# 13_LMS3_Power.net
KiCad netlist of a schematic drawn in Altium Designer
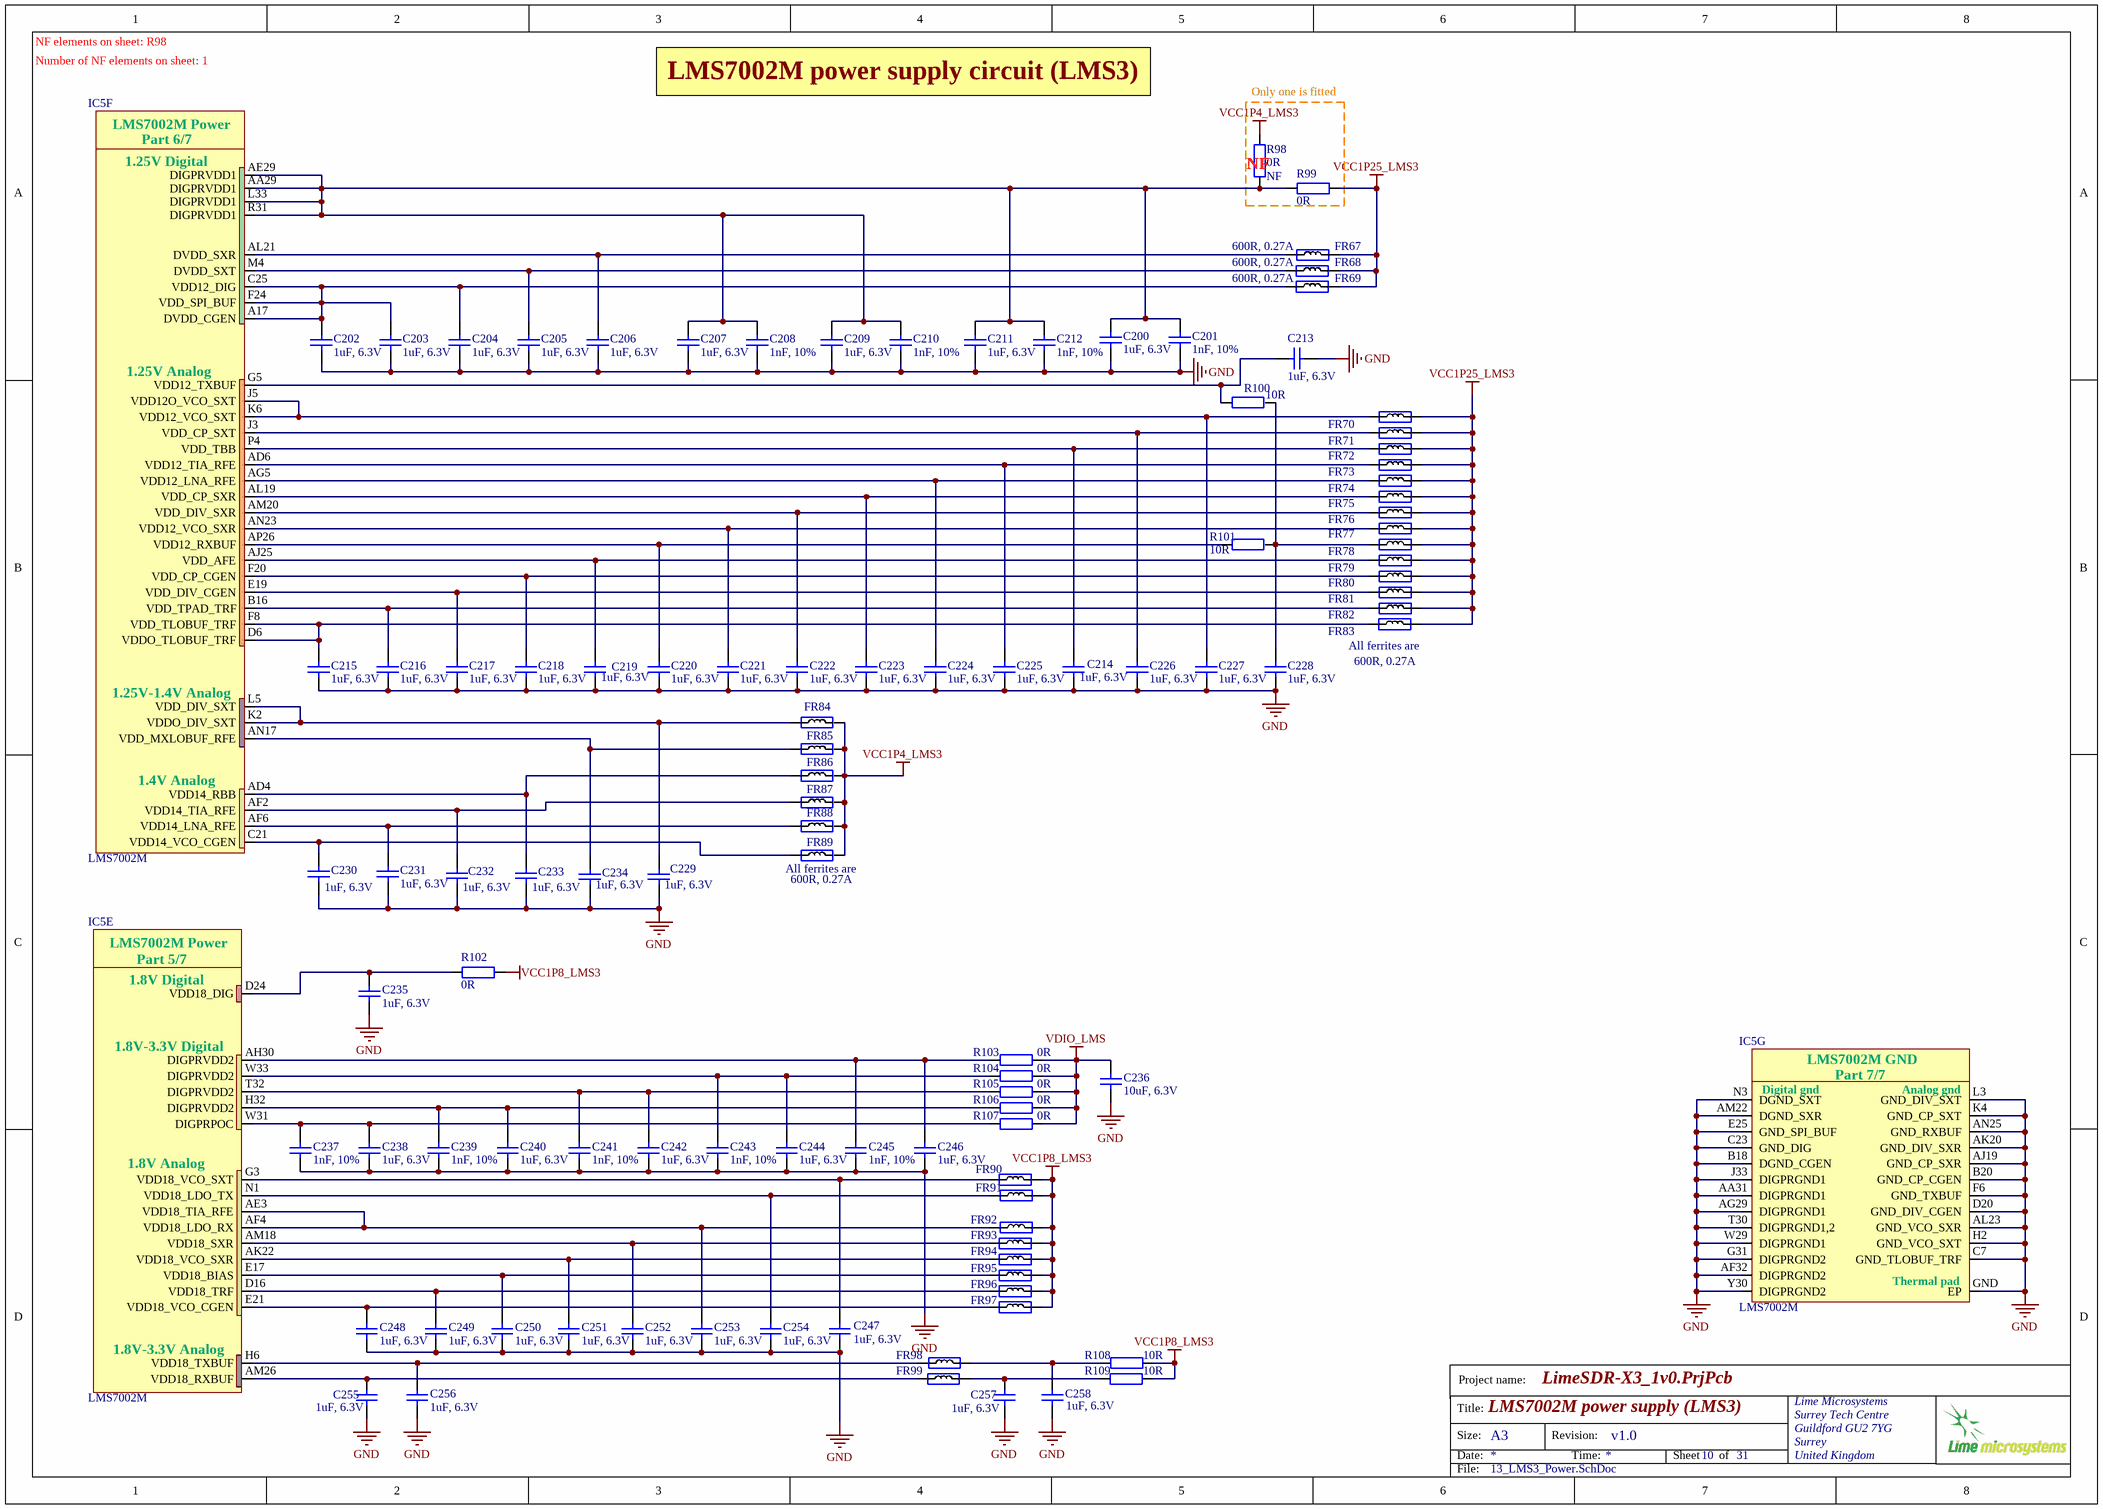
[diagram p0: 13_LMS3_Power.SchDoc]

(export (version "E")
  (design (tool "Eeschema 10.0.6"))
  (components
    (comp (ref "C200")
      (value "1uF, 6.3V")
      (footprint "CAP0201")
      (fields (field (name "TOLERANCE") "±20%") (field (name "MANUFACTURER") "TDK Corporation"))
      (libsource (lib "") (part "Cap_0402_1"))
    )
    (comp (ref "C201")
      (value "1nF, 10%")
      (footprint "CAP0201")
      (fields (field (name "TOLERANCE") "±10%") (field (name "MANUFACTURER") "TDK Corporation"))
      (libsource (lib "") (part "Cap_0402_1"))
    )
    (comp (ref "C202")
      (value "1uF, 6.3V")
      (footprint "CAP0201")
      (fields (field (name "TOLERANCE") "±20%") (field (name "MANUFACTURER") "TDK Corporation"))
      (libsource (lib "") (part "Cap_0402_2"))
    )
    (comp (ref "C203")
      (value "1uF, 6.3V")
      (footprint "CAP0201")
      (fields (field (name "TOLERANCE") "±20%") (field (name "MANUFACTURER") "TDK Corporation"))
      (libsource (lib "") (part "Cap_0402_2"))
    )
    (comp (ref "C204")
      (value "1uF, 6.3V")
      (footprint "CAP0201")
      (fields (field (name "TOLERANCE") "±20%") (field (name "MANUFACTURER") "TDK Corporation"))
      (libsource (lib "") (part "Cap_0402_2"))
    )
    (comp (ref "C205")
      (value "1uF, 6.3V")
      (footprint "CAP0201")
      (fields (field (name "TOLERANCE") "±20%") (field (name "MANUFACTURER") "TDK Corporation"))
      (libsource (lib "") (part "Cap_0402_1"))
    )
    (comp (ref "C206")
      (value "1uF, 6.3V")
      (footprint "CAP0201")
      (fields (field (name "TOLERANCE") "±20%") (field (name "MANUFACTURER") "TDK Corporation"))
      (libsource (lib "") (part "Cap_0402_2"))
    )
    (comp (ref "C207")
      (value "1uF, 6.3V")
      (footprint "CAP0201")
      (fields (field (name "TOLERANCE") "±20%") (field (name "MANUFACTURER") "TDK Corporation"))
      (libsource (lib "") (part "Cap_0402_1"))
    )
    (comp (ref "C208")
      (value "1nF, 10%")
      (footprint "CAP0201")
      (fields (field (name "TOLERANCE") "±10%") (field (name "MANUFACTURER") "TDK Corporation"))
      (libsource (lib "") (part "Cap_0402_1"))
    )
    (comp (ref "C209")
      (value "1uF, 6.3V")
      (footprint "CAP0201")
      (fields (field (name "TOLERANCE") "±20%") (field (name "MANUFACTURER") "TDK Corporation"))
      (libsource (lib "") (part "Cap_0402_1"))
    )
    (comp (ref "C210")
      (value "1nF, 10%")
      (footprint "CAP0201")
      (fields (field (name "TOLERANCE") "±10%") (field (name "MANUFACTURER") "TDK Corporation"))
      (libsource (lib "") (part "Cap_0402_1"))
    )
    (comp (ref "C211")
      (value "1uF, 6.3V")
      (footprint "CAP0201")
      (fields (field (name "TOLERANCE") "±20%") (field (name "MANUFACTURER") "TDK Corporation"))
      (libsource (lib "") (part "Cap_0402_1"))
    )
    (comp (ref "C212")
      (value "1nF, 10%")
      (footprint "CAP0201")
      (fields (field (name "TOLERANCE") "±10%") (field (name "MANUFACTURER") "TDK Corporation"))
      (libsource (lib "") (part "Cap_0402_1"))
    )
    (comp (ref "C213")
      (value "1uF, 6.3V")
      (footprint "CAP0201")
      (fields (field (name "TOLERANCE") "±20%") (field (name "MANUFACTURER") "TDK Corporation"))
      (libsource (lib "") (part "Cap_0402_4"))
    )
    (comp (ref "C214")
      (value "1uF, 6.3V")
      (footprint "CAP0201")
      (fields (field (name "TOLERANCE") "±20%") (field (name "MANUFACTURER") "TDK Corporation"))
      (libsource (lib "") (part "Cap_0402_2"))
    )
    (comp (ref "C215")
      (value "1uF, 6.3V")
      (footprint "CAP0201")
      (fields (field (name "TOLERANCE") "±20%") (field (name "MANUFACTURER") "TDK Corporation"))
      (libsource (lib "") (part "Cap_0402_2"))
    )
    (comp (ref "C216")
      (value "1uF, 6.3V")
      (footprint "CAP0201")
      (fields (field (name "TOLERANCE") "±20%") (field (name "MANUFACTURER") "TDK Corporation"))
      (libsource (lib "") (part "Cap_0402_2"))
    )
    (comp (ref "C217")
      (value "1uF, 6.3V")
      (footprint "CAP0201")
      (fields (field (name "TOLERANCE") "±20%") (field (name "MANUFACTURER") "TDK Corporation"))
      (libsource (lib "") (part "Cap_0402_2"))
    )
    (comp (ref "C218")
      (value "1uF, 6.3V")
      (footprint "CAP0201")
      (fields (field (name "TOLERANCE") "±20%") (field (name "MANUFACTURER") "TDK Corporation"))
      (libsource (lib "") (part "Cap_0402_1"))
    )
    (comp (ref "C219")
      (value "1uF, 6.3V")
      (footprint "CAP0201")
      (fields (field (name "TOLERANCE") "±20%") (field (name "MANUFACTURER") "TDK Corporation"))
      (libsource (lib "") (part "Cap_0402_2"))
    )
    (comp (ref "C220")
      (value "1uF, 6.3V")
      (footprint "CAP0201")
      (fields (field (name "TOLERANCE") "±20%") (field (name "MANUFACTURER") "TDK Corporation"))
      (libsource (lib "") (part "Cap_0402_2"))
    )
    (comp (ref "C221")
      (value "1uF, 6.3V")
      (footprint "CAP0201")
      (fields (field (name "TOLERANCE") "±20%") (field (name "MANUFACTURER") "TDK Corporation"))
      (libsource (lib "") (part "Cap_0402_2"))
    )
    (comp (ref "C222")
      (value "1uF, 6.3V")
      (footprint "CAP0201")
      (fields (field (name "TOLERANCE") "±20%") (field (name "MANUFACTURER") "TDK Corporation"))
      (libsource (lib "") (part "Cap_0402_2"))
    )
    (comp (ref "C223")
      (value "1uF, 6.3V")
      (footprint "CAP0201")
      (fields (field (name "TOLERANCE") "±20%") (field (name "MANUFACTURER") "TDK Corporation"))
      (libsource (lib "") (part "Cap_0402_2"))
    )
    (comp (ref "C224")
      (value "1uF, 6.3V")
      (footprint "CAP0201")
      (fields (field (name "TOLERANCE") "±20%") (field (name "MANUFACTURER") "TDK Corporation"))
      (libsource (lib "") (part "Cap_0402_2"))
    )
    (comp (ref "C225")
      (value "1uF, 6.3V")
      (footprint "CAP0201")
      (fields (field (name "TOLERANCE") "±20%") (field (name "MANUFACTURER") "TDK Corporation"))
      (libsource (lib "") (part "Cap_0402_1"))
    )
    (comp (ref "C226")
      (value "1uF, 6.3V")
      (footprint "CAP0201")
      (fields (field (name "TOLERANCE") "±20%") (field (name "MANUFACTURER") "TDK Corporation"))
      (libsource (lib "") (part "Cap_0402_2"))
    )
    (comp (ref "C227")
      (value "1uF, 6.3V")
      (footprint "CAP0201")
      (fields (field (name "TOLERANCE") "±20%") (field (name "MANUFACTURER") "TDK Corporation"))
      (libsource (lib "") (part "Cap_0402_1"))
    )
    (comp (ref "C228")
      (value "1uF, 6.3V")
      (footprint "CAP0201")
      (fields (field (name "TOLERANCE") "±20%") (field (name "MANUFACTURER") "TDK Corporation"))
      (libsource (lib "") (part "Cap_0402_1"))
    )
    (comp (ref "C229")
      (value "1uF, 6.3V")
      (footprint "CAP0201")
      (fields (field (name "TOLERANCE") "±20%") (field (name "MANUFACTURER") "TDK Corporation"))
      (libsource (lib "") (part "Cap_0402_2"))
    )
    (comp (ref "C230")
      (value "1uF, 6.3V")
      (footprint "CAP0201")
      (fields (field (name "TOLERANCE") "±20%") (field (name "MANUFACTURER") "TDK Corporation"))
      (libsource (lib "") (part "Cap_0402_2"))
    )
    (comp (ref "C231")
      (value "1uF, 6.3V")
      (footprint "CAP0201")
      (fields (field (name "TOLERANCE") "±20%") (field (name "MANUFACTURER") "TDK Corporation"))
      (libsource (lib "") (part "Cap_0402_2"))
    )
    (comp (ref "C232")
      (value "1uF, 6.3V")
      (footprint "CAP0201")
      (fields (field (name "TOLERANCE") "±20%") (field (name "MANUFACTURER") "TDK Corporation"))
      (libsource (lib "LimeMicroAltiumLib_schLib") (part "Cap_0402"))
    )
    (comp (ref "C233")
      (value "1uF, 6.3V")
      (footprint "CAP0201")
      (fields (field (name "TOLERANCE") "±20%") (field (name "MANUFACTURER") "TDK Corporation"))
      (libsource (lib "LimeMicroAltiumLib_schLib") (part "Cap_0402"))
    )
    (comp (ref "C234")
      (value "1uF, 6.3V")
      (footprint "CAP0201")
      (fields (field (name "TOLERANCE") "±20%") (field (name "MANUFACTURER") "TDK Corporation"))
      (libsource (lib "") (part "Cap_0402_2"))
    )
    (comp (ref "C235")
      (value "1uF, 6.3V")
      (footprint "CAP0201")
      (fields (field (name "TOLERANCE") "±20%") (field (name "MANUFACTURER") "TDK Corporation"))
      (libsource (lib "") (part "Cap_0402_3"))
    )
    (comp (ref "C236")
      (value "10uF, 6.3V")
      (footprint "CAP0603")
      (fields (field (name "TOLERANCE") "±20%") (field (name "MANUFACTURER") "Yageo"))
      (libsource (lib "LimeFPGAboard_schLib") (part "Cap_0603"))
    )
    (comp (ref "C237")
      (value "1nF, 10%")
      (footprint "CAP0201")
      (fields (field (name "TOLERANCE") "±10%") (field (name "MANUFACTURER") "TDK Corporation"))
      (libsource (lib "") (part "Cap_0402_3"))
    )
    (comp (ref "C238")
      (value "1uF, 6.3V")
      (footprint "CAP0201")
      (fields (field (name "TOLERANCE") "±20%") (field (name "MANUFACTURER") "TDK Corporation"))
      (libsource (lib "") (part "Cap_0402_3"))
    )
    (comp (ref "C239")
      (value "1nF, 10%")
      (footprint "CAP0201")
      (fields (field (name "TOLERANCE") "±10%") (field (name "MANUFACTURER") "TDK Corporation"))
      (libsource (lib "") (part "Cap_0402_3"))
    )
    (comp (ref "C240")
      (value "1uF, 6.3V")
      (footprint "CAP0201")
      (fields (field (name "TOLERANCE") "±20%") (field (name "MANUFACTURER") "TDK Corporation"))
      (libsource (lib "") (part "Cap_0402_3"))
    )
    (comp (ref "C241")
      (value "1nF, 10%")
      (footprint "CAP0201")
      (fields (field (name "TOLERANCE") "±10%") (field (name "MANUFACTURER") "TDK Corporation"))
      (libsource (lib "") (part "Cap_0402_3"))
    )
    (comp (ref "C242")
      (value "1uF, 6.3V")
      (footprint "CAP0201")
      (fields (field (name "TOLERANCE") "±20%") (field (name "MANUFACTURER") "TDK Corporation"))
      (libsource (lib "") (part "Cap_0402_3"))
    )
    (comp (ref "C243")
      (value "1nF, 10%")
      (footprint "CAP0201")
      (fields (field (name "TOLERANCE") "±10%") (field (name "MANUFACTURER") "TDK Corporation"))
      (libsource (lib "") (part "Cap_0402_3"))
    )
    (comp (ref "C244")
      (value "1uF, 6.3V")
      (footprint "CAP0201")
      (fields (field (name "TOLERANCE") "±20%") (field (name "MANUFACTURER") "TDK Corporation"))
      (libsource (lib "") (part "Cap_0402_3"))
    )
    (comp (ref "C245")
      (value "1nF, 10%")
      (footprint "CAP0201")
      (fields (field (name "TOLERANCE") "±10%") (field (name "MANUFACTURER") "TDK Corporation"))
      (libsource (lib "") (part "Cap_0402_3"))
    )
    (comp (ref "C246")
      (value "1uF, 6.3V")
      (footprint "CAP0201")
      (fields (field (name "TOLERANCE") "±20%") (field (name "MANUFACTURER") "TDK Corporation"))
      (libsource (lib "") (part "Cap_0402_3"))
    )
    (comp (ref "C247")
      (value "1uF, 6.3V")
      (footprint "CAP0201")
      (fields (field (name "TOLERANCE") "±20%") (field (name "MANUFACTURER") "TDK Corporation"))
      (libsource (lib "") (part "Cap_0402_3"))
    )
    (comp (ref "C248")
      (value "1uF, 6.3V")
      (footprint "CAP0201")
      (fields (field (name "TOLERANCE") "±20%") (field (name "MANUFACTURER") "TDK Corporation"))
      (libsource (lib "") (part "Cap_0402_3"))
    )
    (comp (ref "C249")
      (value "1uF, 6.3V")
      (footprint "CAP0201")
      (fields (field (name "TOLERANCE") "±20%") (field (name "MANUFACTURER") "TDK Corporation"))
      (libsource (lib "") (part "Cap_0402_3"))
    )
    (comp (ref "C250")
      (value "1uF, 6.3V")
      (footprint "CAP0201")
      (fields (field (name "TOLERANCE") "±20%") (field (name "MANUFACTURER") "TDK Corporation"))
      (libsource (lib "") (part "Cap_0402_3"))
    )
    (comp (ref "C251")
      (value "1uF, 6.3V")
      (footprint "CAP0201")
      (fields (field (name "TOLERANCE") "±20%") (field (name "MANUFACTURER") "TDK Corporation"))
      (libsource (lib "") (part "Cap_0402_3"))
    )
    (comp (ref "C252")
      (value "1uF, 6.3V")
      (footprint "CAP0201")
      (fields (field (name "TOLERANCE") "±20%") (field (name "MANUFACTURER") "TDK Corporation"))
      (libsource (lib "") (part "Cap_0402_3"))
    )
    (comp (ref "C253")
      (value "1uF, 6.3V")
      (footprint "CAP0201")
      (fields (field (name "TOLERANCE") "±20%") (field (name "MANUFACTURER") "TDK Corporation"))
      (libsource (lib "") (part "Cap_0402_3"))
    )
    (comp (ref "C254")
      (value "1uF, 6.3V")
      (footprint "CAP0201")
      (fields (field (name "TOLERANCE") "±20%") (field (name "MANUFACTURER") "TDK Corporation"))
      (libsource (lib "") (part "Cap_0402_3"))
    )
    (comp (ref "C255")
      (value "1uF, 6.3V")
      (footprint "CAP0201")
      (fields (field (name "TOLERANCE") "±20%") (field (name "MANUFACTURER") "TDK Corporation"))
      (libsource (lib "") (part "Cap_0402_3"))
    )
    (comp (ref "C256")
      (value "1uF, 6.3V")
      (footprint "CAP0201")
      (fields (field (name "TOLERANCE") "±20%") (field (name "MANUFACTURER") "TDK Corporation"))
      (libsource (lib "") (part "Cap_0402_3"))
    )
    (comp (ref "C257")
      (value "1uF, 6.3V")
      (footprint "CAP0201")
      (fields (field (name "TOLERANCE") "±20%") (field (name "MANUFACTURER") "TDK Corporation"))
      (libsource (lib "") (part "Cap_0402_3"))
    )
    (comp (ref "C258")
      (value "1uF, 6.3V")
      (footprint "CAP0201")
      (fields (field (name "TOLERANCE") "±20%") (field (name "MANUFACTURER") "TDK Corporation"))
      (libsource (lib "") (part "Cap_0402_3"))
    )
    (comp (ref "FR67")
      (value "600R, 0.27A")
      (footprint "RES0201")
      (fields (field (name "MANUFACTURER") "Taiyo Yuden"))
      (libsource (lib "LimeMicroAltiumLib_schLib") (part "Ferrite"))
    )
    (comp (ref "FR68")
      (value "600R, 0.27A")
      (footprint "RES0201")
      (fields (field (name "MANUFACTURER") "Taiyo Yuden"))
      (libsource (lib "") (part "Ferrite_1"))
    )
    (comp (ref "FR69")
      (value "600R, 0.27A")
      (footprint "RES0201")
      (fields (field (name "MANUFACTURER") "Taiyo Yuden"))
      (libsource (lib "") (part "Ferrite_1"))
    )
    (comp (ref "FR70")
      (value "600R, 0.27A")
      (footprint "RES0201")
      (fields (field (name "MANUFACTURER") "Taiyo Yuden"))
      (libsource (lib "LimeMicroAltiumLib_schLib") (part "Ferrite"))
    )
    (comp (ref "FR71")
      (value "600R, 0.27A")
      (footprint "RES0201")
      (fields (field (name "MANUFACTURER") "Taiyo Yuden"))
      (libsource (lib "LimeMicroAltiumLib_schLib") (part "Ferrite"))
    )
    (comp (ref "FR72")
      (value "600R, 0.27A")
      (footprint "RES0201")
      (fields (field (name "MANUFACTURER") "Taiyo Yuden"))
      (libsource (lib "LimeMicroAltiumLib_schLib") (part "Ferrite"))
    )
    (comp (ref "FR73")
      (value "600R, 0.27A")
      (footprint "RES0201")
      (fields (field (name "MANUFACTURER") "Taiyo Yuden"))
      (libsource (lib "LimeMicroAltiumLib_schLib") (part "Ferrite"))
    )
    (comp (ref "FR74")
      (value "600R, 0.27A")
      (footprint "RES0201")
      (fields (field (name "MANUFACTURER") "Taiyo Yuden"))
      (libsource (lib "LimeMicroAltiumLib_schLib") (part "Ferrite"))
    )
    (comp (ref "FR75")
      (value "600R, 0.27A")
      (footprint "RES0201")
      (fields (field (name "MANUFACTURER") "Taiyo Yuden"))
      (libsource (lib "LimeMicroAltiumLib_schLib") (part "Ferrite"))
    )
    (comp (ref "FR76")
      (value "600R, 0.27A")
      (footprint "RES0201")
      (fields (field (name "MANUFACTURER") "Taiyo Yuden"))
      (libsource (lib "LimeMicroAltiumLib_schLib") (part "Ferrite"))
    )
    (comp (ref "FR77")
      (value "600R, 0.27A")
      (footprint "RES0201")
      (fields (field (name "MANUFACTURER") "Taiyo Yuden"))
      (libsource (lib "LimeMicroAltiumLib_schLib") (part "Ferrite"))
    )
    (comp (ref "FR78")
      (value "600R, 0.27A")
      (footprint "RES0201")
      (fields (field (name "MANUFACTURER") "Taiyo Yuden"))
      (libsource (lib "LimeMicroAltiumLib_schLib") (part "Ferrite"))
    )
    (comp (ref "FR79")
      (value "600R, 0.27A")
      (footprint "RES0201")
      (fields (field (name "MANUFACTURER") "Taiyo Yuden"))
      (libsource (lib "LimeMicroAltiumLib_schLib") (part "Ferrite"))
    )
    (comp (ref "FR80")
      (value "600R, 0.27A")
      (footprint "RES0201")
      (fields (field (name "MANUFACTURER") "Taiyo Yuden"))
      (libsource (lib "LimeMicroAltiumLib_schLib") (part "Ferrite"))
    )
    (comp (ref "FR81")
      (value "600R, 0.27A")
      (footprint "RES0201")
      (fields (field (name "MANUFACTURER") "Taiyo Yuden"))
      (libsource (lib "LimeMicroAltiumLib_schLib") (part "Ferrite"))
    )
    (comp (ref "FR82")
      (value "600R, 0.27A")
      (footprint "RES0201")
      (fields (field (name "MANUFACTURER") "Taiyo Yuden"))
      (libsource (lib "LimeMicroAltiumLib_schLib") (part "Ferrite"))
    )
    (comp (ref "FR83")
      (value "600R, 0.27A")
      (footprint "RES0201")
      (fields (field (name "MANUFACTURER") "Taiyo Yuden"))
      (libsource (lib "") (part "Ferrite_1"))
    )
    (comp (ref "FR84")
      (value "600R, 0.27A")
      (footprint "RES0201")
      (fields (field (name "MANUFACTURER") "Taiyo Yuden"))
      (libsource (lib "") (part "Ferrite_1"))
    )
    (comp (ref "FR85")
      (value "600R, 0.27A")
      (footprint "RES0201")
      (fields (field (name "MANUFACTURER") "Taiyo Yuden"))
      (libsource (lib "") (part "Ferrite_1"))
    )
    (comp (ref "FR86")
      (value "600R, 0.27A")
      (footprint "RES0201")
      (fields (field (name "MANUFACTURER") "Taiyo Yuden"))
      (libsource (lib "") (part "Ferrite_1"))
    )
    (comp (ref "FR87")
      (value "600R, 0.27A")
      (footprint "RES0201")
      (fields (field (name "MANUFACTURER") "Taiyo Yuden"))
      (libsource (lib "") (part "Ferrite_1"))
    )
    (comp (ref "FR88")
      (value "600R, 0.27A")
      (footprint "RES0201")
      (fields (field (name "MANUFACTURER") "Taiyo Yuden"))
      (libsource (lib "") (part "Ferrite_1"))
    )
    (comp (ref "FR89")
      (value "600R, 0.27A")
      (footprint "RES0201")
      (fields (field (name "MANUFACTURER") "Taiyo Yuden"))
      (libsource (lib "") (part "Ferrite_1"))
    )
    (comp (ref "FR90")
      (value "600R, 0.27A")
      (footprint "RES0201")
      (fields (field (name "MANUFACTURER") "Taiyo Yuden"))
      (libsource (lib "") (part "Ferrite_1"))
    )
    (comp (ref "FR91")
      (value "600R, 0.27A")
      (footprint "RES0201")
      (fields (field (name "MANUFACTURER") "Taiyo Yuden"))
      (libsource (lib "") (part "Ferrite_2"))
    )
    (comp (ref "FR92")
      (value "600R, 0.27A")
      (footprint "RES0201")
      (fields (field (name "MANUFACTURER") "Taiyo Yuden"))
      (libsource (lib "") (part "Ferrite_2"))
    )
    (comp (ref "FR93")
      (value "600R, 0.27A")
      (footprint "RES0201")
      (fields (field (name "MANUFACTURER") "Taiyo Yuden"))
      (libsource (lib "") (part "Ferrite_1"))
    )
    (comp (ref "FR94")
      (value "600R, 0.27A")
      (footprint "RES0201")
      (fields (field (name "MANUFACTURER") "Taiyo Yuden"))
      (libsource (lib "") (part "Ferrite_1"))
    )
    (comp (ref "FR95")
      (value "600R, 0.27A")
      (footprint "RES0201")
      (fields (field (name "MANUFACTURER") "Taiyo Yuden"))
      (libsource (lib "") (part "Ferrite_1"))
    )
    (comp (ref "FR96")
      (value "600R, 0.27A")
      (footprint "RES0201")
      (fields (field (name "MANUFACTURER") "Taiyo Yuden"))
      (libsource (lib "") (part "Ferrite_1"))
    )
    (comp (ref "FR97")
      (value "600R, 0.27A")
      (footprint "RES0201")
      (fields (field (name "MANUFACTURER") "Taiyo Yuden"))
      (libsource (lib "") (part "Ferrite_1"))
    )
    (comp (ref "FR98")
      (value "600R, 0.27A")
      (footprint "RES0201")
      (fields (field (name "MANUFACTURER") "Taiyo Yuden"))
      (libsource (lib "") (part "Ferrite_2"))
    )
    (comp (ref "FR99")
      (value "600R, 0.27A")
      (footprint "RES0201")
      (fields (field (name "MANUFACTURER") "Taiyo Yuden"))
      (libsource (lib "") (part "Ferrite_1"))
    )
    (comp (ref "IC5")
      (value "LMS7002M")
      (footprint "LMS7002M_v5")
      (description "Schematic symbol revision 4. Default footprint - 0.31mm pad")
      (fields (field (name "MANUFACTURER") "Lime Microsystems"))
      (libsource (lib "LimeMicroAltiumLib_schLib_r04") (part "LMS7002Mr4"))
    )
    (comp (ref "R98")
      (value "0R")
      (footprint "RES0402")
      (fields
        (field (name "ASSEMBLY INFO") "NF")
        (field (name "MANUFACTURER") "Yageo")
        (field (name "TOLERANCE") "Jumper")
      )
      (libsource (lib "LimeMicroAltiumLib_schLib") (part "Res_0402"))
    )
    (comp (ref "R99")
      (value "0R")
      (footprint "RES0402")
      (fields (field (name "MANUFACTURER") "Yageo") (field (name "TOLERANCE") "Jumper"))
      (libsource (lib "") (part "Res_0402_1"))
    )
    (comp (ref "R100")
      (value "10R")
      (footprint "RES0201")
      (fields
        (field (name "MANUFACTURER") "Panasonic Electronic Components")
        (field (name "TOLERANCE") "±1%")
      )
      (libsource (lib "LimeMicroAltiumLib_schLib") (part "Res_0402"))
    )
    (comp (ref "R101")
      (value "10R")
      (footprint "RES0201")
      (fields
        (field (name "MANUFACTURER") "Panasonic Electronic Components")
        (field (name "TOLERANCE") "±1%")
      )
      (libsource (lib "LimeMicroAltiumLib_schLib") (part "Res_0402"))
    )
    (comp (ref "R102")
      (value "0R")
      (footprint "RES0201")
      (fields (field (name "MANUFACTURER") "Rohm Semiconductor") (field (name "TOLERANCE") "Jumper"))
      (libsource (lib "LimeMicroAltiumLib_schLib") (part "Res_0402"))
    )
    (comp (ref "R103")
      (value "0R")
      (footprint "RES0402")
      (fields (field (name "MANUFACTURER") "Yageo") (field (name "TOLERANCE") "Jumper"))
      (libsource (lib "LimeMicroAltiumLib_schLib") (part "Res_0402"))
    )
    (comp (ref "R104")
      (value "0R")
      (footprint "RES0402")
      (fields (field (name "MANUFACTURER") "Yageo") (field (name "TOLERANCE") "Jumper"))
      (libsource (lib "LimeMicroAltiumLib_schLib") (part "Res_0402"))
    )
    (comp (ref "R105")
      (value "0R")
      (footprint "RES0402")
      (fields (field (name "MANUFACTURER") "Yageo") (field (name "TOLERANCE") "Jumper"))
      (libsource (lib "LimeMicroAltiumLib_schLib") (part "Res_0402"))
    )
    (comp (ref "R106")
      (value "0R")
      (footprint "RES0402")
      (fields (field (name "MANUFACTURER") "Yageo") (field (name "TOLERANCE") "Jumper"))
      (libsource (lib "LimeMicroAltiumLib_schLib") (part "Res_0402"))
    )
    (comp (ref "R107")
      (value "0R")
      (footprint "RES0402")
      (fields (field (name "MANUFACTURER") "Yageo") (field (name "TOLERANCE") "Jumper"))
      (libsource (lib "LimeMicroAltiumLib_schLib") (part "Res_0402"))
    )
    (comp (ref "R108")
      (value "10R")
      (footprint "RES0201")
      (fields
        (field (name "MANUFACTURER") "Panasonic Electronic Components")
        (field (name "TOLERANCE") "±1%")
      )
      (libsource (lib "LimeMicroAltiumLib_schLib") (part "Res_0402"))
    )
    (comp (ref "R109")
      (value "10R")
      (footprint "RES0201")
      (fields
        (field (name "MANUFACTURER") "Panasonic Electronic Components")
        (field (name "TOLERANCE") "±1%")
      )
      (libsource (lib "LimeMicroAltiumLib_schLib") (part "Res_0402"))
    )
  )
  (nets
    (net (code "1") (name "GND") (class "Default")
      (node (ref "C200") (pin "2") (pinfunction "2_2") (pintype "passive"))
      (node (ref "C201") (pin "2") (pinfunction "2_2") (pintype "passive"))
      (node (ref "C202") (pin "2") (pinfunction "2_2") (pintype "passive"))
      (node (ref "C203") (pin "2") (pinfunction "2_2") (pintype "passive"))
      (node (ref "C204") (pin "2") (pinfunction "2_2") (pintype "passive"))
      (node (ref "C205") (pin "1") (pinfunction "1_1") (pintype "passive"))
      (node (ref "C206") (pin "2") (pinfunction "2_2") (pintype "passive"))
      (node (ref "C207") (pin "2") (pinfunction "2_2") (pintype "passive"))
      (node (ref "C208") (pin "2") (pinfunction "2_2") (pintype "passive"))
      (node (ref "C209") (pin "2") (pinfunction "2_2") (pintype "passive"))
      (node (ref "C210") (pin "2") (pinfunction "2_2") (pintype "passive"))
      (node (ref "C211") (pin "2") (pinfunction "2_2") (pintype "passive"))
      (node (ref "C212") (pin "2") (pinfunction "2_2") (pintype "passive"))
      (node (ref "C213") (pin "2") (pinfunction "2_2") (pintype "passive"))
      (node (ref "C214") (pin "2") (pinfunction "2_2") (pintype "passive"))
      (node (ref "C215") (pin "2") (pinfunction "2_2") (pintype "passive"))
      (node (ref "C216") (pin "2") (pinfunction "2_2") (pintype "passive"))
      (node (ref "C217") (pin "2") (pinfunction "2_2") (pintype "passive"))
      (node (ref "C218") (pin "1") (pinfunction "1_1") (pintype "passive"))
      (node (ref "C219") (pin "2") (pinfunction "2_2") (pintype "passive"))
      (node (ref "C220") (pin "2") (pinfunction "2_2") (pintype "passive"))
      (node (ref "C221") (pin "2") (pinfunction "2_2") (pintype "passive"))
      (node (ref "C222") (pin "2") (pinfunction "2_2") (pintype "passive"))
      (node (ref "C223") (pin "2") (pinfunction "2_2") (pintype "passive"))
      (node (ref "C224") (pin "2") (pinfunction "2_2") (pintype "passive"))
      (node (ref "C225") (pin "1") (pinfunction "1_1") (pintype "passive"))
      (node (ref "C226") (pin "2") (pinfunction "2_2") (pintype "passive"))
      (node (ref "C227") (pin "1") (pinfunction "1_1") (pintype "passive"))
      (node (ref "C228") (pin "1") (pinfunction "1_1") (pintype "passive"))
      (node (ref "C229") (pin "2") (pinfunction "2_2") (pintype "passive"))
      (node (ref "C230") (pin "2") (pinfunction "2_2") (pintype "passive"))
      (node (ref "C231") (pin "2") (pinfunction "2_2") (pintype "passive"))
      (node (ref "C232") (pin "2") (pinfunction "2_2") (pintype "passive"))
      (node (ref "C233") (pin "2") (pinfunction "2_2") (pintype "passive"))
      (node (ref "C234") (pin "2") (pinfunction "2_2") (pintype "passive"))
      (node (ref "C235") (pin "2") (pinfunction "2_2") (pintype "passive"))
      (node (ref "C236") (pin "1") (pinfunction "1_1") (pintype "passive"))
      (node (ref "C237") (pin "2") (pinfunction "2_2") (pintype "passive"))
      (node (ref "C238") (pin "2") (pinfunction "2_2") (pintype "passive"))
      (node (ref "C239") (pin "2") (pinfunction "2_2") (pintype "passive"))
      (node (ref "C240") (pin "2") (pinfunction "2_2") (pintype "passive"))
      (node (ref "C241") (pin "2") (pinfunction "2_2") (pintype "passive"))
      (node (ref "C242") (pin "2") (pinfunction "2_2") (pintype "passive"))
      (node (ref "C243") (pin "2") (pinfunction "2_2") (pintype "passive"))
      (node (ref "C244") (pin "2") (pinfunction "2_2") (pintype "passive"))
      (node (ref "C245") (pin "2") (pinfunction "2_2") (pintype "passive"))
      (node (ref "C246") (pin "2") (pinfunction "2_2") (pintype "passive"))
      (node (ref "C247") (pin "2") (pinfunction "2_2") (pintype "passive"))
      (node (ref "C248") (pin "2") (pinfunction "2_2") (pintype "passive"))
      (node (ref "C249") (pin "2") (pinfunction "2_2") (pintype "passive"))
      (node (ref "C250") (pin "2") (pinfunction "2_2") (pintype "passive"))
      (node (ref "C251") (pin "2") (pinfunction "2_2") (pintype "passive"))
      (node (ref "C252") (pin "2") (pinfunction "2_2") (pintype "passive"))
      (node (ref "C253") (pin "2") (pinfunction "2_2") (pintype "passive"))
      (node (ref "C254") (pin "2") (pinfunction "2_2") (pintype "passive"))
      (node (ref "C255") (pin "2") (pinfunction "2_2") (pintype "passive"))
      (node (ref "C256") (pin "2") (pinfunction "2_2") (pintype "passive"))
      (node (ref "C257") (pin "2") (pinfunction "2_2") (pintype "passive"))
      (node (ref "C258") (pin "2") (pinfunction "2_2") (pintype "passive"))
      (node (ref "IC5") (pin "AA31") (pinfunction "DIGPRGND1_AA31") (pintype "passive"))
      (node (ref "IC5") (pin "AF32") (pinfunction "DIGPRGND2_AF32") (pintype "passive"))
      (node (ref "IC5") (pin "AG29") (pinfunction "DIGPRGND1_AG29") (pintype "passive"))
      (node (ref "IC5") (pin "AJ19") (pinfunction "GND_CP_SXR_AJ19") (pintype "passive"))
      (node (ref "IC5") (pin "AK20") (pinfunction "GND_DIV_SXR_AK20") (pintype "passive"))
      (node (ref "IC5") (pin "AL23") (pinfunction "GND_VCO_SXR_AL23") (pintype "passive"))
      (node (ref "IC5") (pin "AM22") (pinfunction "DGND_SXR_AM22") (pintype "passive"))
      (node (ref "IC5") (pin "AN25") (pinfunction "GND_RXBUF_AN25") (pintype "passive"))
      (node (ref "IC5") (pin "B18") (pinfunction "DGND_CGEN_B18") (pintype "passive"))
      (node (ref "IC5") (pin "B20") (pinfunction "GND_CP_CGEN_B20") (pintype "passive"))
      (node (ref "IC5") (pin "C23") (pinfunction "GND_DIG_C23") (pintype "passive"))
      (node (ref "IC5") (pin "C7") (pinfunction "GND_TLOBUF_TRF_C7") (pintype "passive"))
      (node (ref "IC5") (pin "D20") (pinfunction "GND_DIV_CGEN_D20") (pintype "passive"))
      (node (ref "IC5") (pin "E25") (pinfunction "GND_SPI_BUF_E25") (pintype "passive"))
      (node (ref "IC5") (pin "F6") (pinfunction "GND_TXBUF_F6") (pintype "passive"))
      (node (ref "IC5") (pin "G31") (pinfunction "DIGPRGND2_G31") (pintype "passive"))
      (node (ref "IC5") (pin "GND") (pinfunction "EP_GND") (pintype "passive"))
      (node (ref "IC5") (pin "H2") (pinfunction "GND_VCO_SXT_H2") (pintype "passive"))
      (node (ref "IC5") (pin "J33") (pinfunction "DIGPRGND1_J33") (pintype "passive"))
      (node (ref "IC5") (pin "K4") (pinfunction "GND_CP_SXT_K4") (pintype "passive"))
      (node (ref "IC5") (pin "L3") (pinfunction "GND_DIV_SXT_L3") (pintype "passive"))
      (node (ref "IC5") (pin "N3") (pinfunction "DGND_SXT_N3") (pintype "passive"))
      (node (ref "IC5") (pin "T30") (pinfunction "DIGPRGND1,2_T30") (pintype "passive"))
      (node (ref "IC5") (pin "W29") (pinfunction "DIGPRGND1_W29") (pintype "passive"))
      (node (ref "IC5") (pin "Y30") (pinfunction "DIGPRGND2_Y30") (pintype "passive"))
    )
    (net (code "2") (name "Net-(C200-Pad1)") (class "Default")
      (node (ref "C200") (pin "1") (pinfunction "1_1") (pintype "passive"))
      (node (ref "C201") (pin "1") (pinfunction "1_1") (pintype "passive"))
      (node (ref "C207") (pin "1") (pinfunction "1_1") (pintype "passive"))
      (node (ref "C208") (pin "1") (pinfunction "1_1") (pintype "passive"))
      (node (ref "C209") (pin "1") (pinfunction "1_1") (pintype "passive"))
      (node (ref "C210") (pin "1") (pinfunction "1_1") (pintype "passive"))
      (node (ref "C211") (pin "1") (pinfunction "1_1") (pintype "passive"))
      (node (ref "C212") (pin "1") (pinfunction "1_1") (pintype "passive"))
      (node (ref "IC5") (pin "AA29") (pinfunction "DIGPRVDD1_AA29") (pintype "power_in"))
      (node (ref "IC5") (pin "AE29") (pinfunction "DIGPRVDD1_AE29") (pintype "power_in"))
      (node (ref "IC5") (pin "L33") (pinfunction "DIGPRVDD1_L33") (pintype "power_in"))
      (node (ref "IC5") (pin "R31") (pinfunction "DIGPRVDD1_R31") (pintype "power_in"))
      (node (ref "R98") (pin "2") (pinfunction "2_2") (pintype "passive"))
      (node (ref "R99") (pin "2") (pinfunction "2_2") (pintype "passive"))
    )
    (net (code "3") (name "Net-(C228-Pad2)") (class "Default")
      (node (ref "C228") (pin "2") (pinfunction "2_2") (pintype "passive"))
      (node (ref "FR78") (pin "1") (pinfunction "1_1") (pintype "passive"))
      (node (ref "R100") (pin "2") (pinfunction "2_2") (pintype "passive"))
      (node (ref "R101") (pin "2") (pinfunction "2_2") (pintype "passive"))
    )
    (net (code "4") (name "Net-(C239-Pad1)") (class "Default")
      (node (ref "C239") (pin "1") (pinfunction "1_1") (pintype "passive"))
      (node (ref "C240") (pin "1") (pinfunction "1_1") (pintype "passive"))
      (node (ref "IC5") (pin "H32") (pinfunction "DIGPRVDD2_H32") (pintype "power_in"))
      (node (ref "R106") (pin "2") (pinfunction "2_2") (pintype "passive"))
    )
    (net (code "5") (name "Net-(C241-Pad1)") (class "Default")
      (node (ref "C241") (pin "1") (pinfunction "1_1") (pintype "passive"))
      (node (ref "C242") (pin "1") (pinfunction "1_1") (pintype "passive"))
      (node (ref "IC5") (pin "T32") (pinfunction "DIGPRVDD2_T32") (pintype "power_in"))
      (node (ref "R105") (pin "2") (pinfunction "2_2") (pintype "passive"))
    )
    (net (code "6") (name "Net-(C243-Pad1)") (class "Default")
      (node (ref "C243") (pin "1") (pinfunction "1_1") (pintype "passive"))
      (node (ref "C244") (pin "1") (pinfunction "1_1") (pintype "passive"))
      (node (ref "IC5") (pin "W33") (pinfunction "DIGPRVDD2_W33") (pintype "power_in"))
      (node (ref "R104") (pin "2") (pinfunction "2_2") (pintype "passive"))
    )
    (net (code "7") (name "Net-(C245-Pad1)") (class "Default")
      (node (ref "C245") (pin "1") (pinfunction "1_1") (pintype "passive"))
      (node (ref "C246") (pin "1") (pinfunction "1_1") (pintype "passive"))
      (node (ref "IC5") (pin "AH30") (pinfunction "DIGPRVDD2_AH30") (pintype "power_in"))
      (node (ref "R103") (pin "2") (pinfunction "2_2") (pintype "passive"))
    )
    (net (code "8") (name "Net-(C257-Pad1)") (class "Default")
      (node (ref "C257") (pin "1") (pinfunction "1_1") (pintype "passive"))
      (node (ref "FR99") (pin "2") (pinfunction "2_2") (pintype "passive"))
      (node (ref "R109") (pin "2") (pinfunction "2_2") (pintype "passive"))
    )
    (net (code "9") (name "Net-(C258-Pad1)") (class "Default")
      (node (ref "C258") (pin "1") (pinfunction "1_1") (pintype "passive"))
      (node (ref "FR98") (pin "1") (pinfunction "1_1") (pintype "passive"))
      (node (ref "R108") (pin "1") (pinfunction "1_1") (pintype "passive"))
    )
    (net (code "10") (name "Net-(IC5E-DIGPRPOC)") (class "Default")
      (node (ref "C237") (pin "1") (pinfunction "1_1") (pintype "passive"))
      (node (ref "C238") (pin "1") (pinfunction "1_1") (pintype "passive"))
      (node (ref "IC5") (pin "W31") (pinfunction "DIGPRPOC_W31") (pintype "power_in"))
      (node (ref "R107") (pin "2") (pinfunction "2_2") (pintype "passive"))
    )
    (net (code "11") (name "Net-(IC5E-VDD18_BIAS)") (class "Default")
      (node (ref "C250") (pin "1") (pinfunction "1_1") (pintype "passive"))
      (node (ref "FR95") (pin "1") (pinfunction "1_1") (pintype "passive"))
      (node (ref "IC5") (pin "E17") (pinfunction "VDD18_BIAS_E17") (pintype "power_in"))
    )
    (net (code "12") (name "Net-(IC5E-VDD18_DIG)") (class "Default")
      (node (ref "C235") (pin "1") (pinfunction "1_1") (pintype "passive"))
      (node (ref "IC5") (pin "D24") (pinfunction "VDD18_DIG_D24") (pintype "power_in"))
      (node (ref "R102") (pin "1") (pinfunction "1_1") (pintype "passive"))
    )
    (net (code "13") (name "Net-(IC5E-VDD18_LDO_RX)") (class "Default")
      (node (ref "C253") (pin "1") (pinfunction "1_1") (pintype "passive"))
      (node (ref "FR92") (pin "2") (pinfunction "2_2") (pintype "passive"))
      (node (ref "IC5") (pin "AE3") (pinfunction "VDD18_TIA_RFE_AE3") (pintype "power_in"))
      (node (ref "IC5") (pin "AF4") (pinfunction "VDD18_LDO_RX_AF4") (pintype "power_in"))
    )
    (net (code "14") (name "Net-(IC5E-VDD18_LDO_TX)") (class "Default")
      (node (ref "C254") (pin "1") (pinfunction "1_1") (pintype "passive"))
      (node (ref "FR91") (pin "2") (pinfunction "2_2") (pintype "passive"))
      (node (ref "IC5") (pin "N1") (pinfunction "VDD18_LDO_TX_N1") (pintype "power_in"))
    )
    (net (code "15") (name "Net-(IC5E-VDD18_RXBUF)") (class "Default")
      (node (ref "C255") (pin "1") (pinfunction "1_1") (pintype "passive"))
      (node (ref "FR99") (pin "1") (pinfunction "1_1") (pintype "passive"))
      (node (ref "IC5") (pin "AM26") (pinfunction "VDD18_RXBUF_AM26") (pintype "power_in"))
    )
    (net (code "16") (name "Net-(IC5E-VDD18_SXR)") (class "Default")
      (node (ref "C252") (pin "1") (pinfunction "1_1") (pintype "passive"))
      (node (ref "FR93") (pin "1") (pinfunction "1_1") (pintype "passive"))
      (node (ref "IC5") (pin "AM18") (pinfunction "VDD18_SXR_AM18") (pintype "power_in"))
    )
    (net (code "17") (name "Net-(IC5E-VDD18_TRF)") (class "Default")
      (node (ref "C249") (pin "1") (pinfunction "1_1") (pintype "passive"))
      (node (ref "FR96") (pin "1") (pinfunction "1_1") (pintype "passive"))
      (node (ref "IC5") (pin "D16") (pinfunction "VDD18_TRF_D16") (pintype "power_in"))
    )
    (net (code "18") (name "Net-(IC5E-VDD18_TXBUF)") (class "Default")
      (node (ref "C256") (pin "1") (pinfunction "1_1") (pintype "passive"))
      (node (ref "FR98") (pin "2") (pinfunction "2_2") (pintype "passive"))
      (node (ref "IC5") (pin "H6") (pinfunction "VDD18_TXBUF_H6") (pintype "power_in"))
    )
    (net (code "19") (name "Net-(IC5E-VDD18_VCO_CGEN)") (class "Default")
      (node (ref "C248") (pin "1") (pinfunction "1_1") (pintype "passive"))
      (node (ref "FR97") (pin "1") (pinfunction "1_1") (pintype "passive"))
      (node (ref "IC5") (pin "E21") (pinfunction "VDD18_VCO_CGEN_E21") (pintype "power_in"))
    )
    (net (code "20") (name "Net-(IC5E-VDD18_VCO_SXR)") (class "Default")
      (node (ref "C251") (pin "1") (pinfunction "1_1") (pintype "passive"))
      (node (ref "FR94") (pin "1") (pinfunction "1_1") (pintype "passive"))
      (node (ref "IC5") (pin "AK22") (pinfunction "VDD18_VCO_SXR_AK22") (pintype "power_in"))
    )
    (net (code "21") (name "Net-(IC5E-VDD18_VCO_SXT)") (class "Default")
      (node (ref "C247") (pin "1") (pinfunction "1_1") (pintype "passive"))
      (node (ref "FR90") (pin "1") (pinfunction "1_1") (pintype "passive"))
      (node (ref "IC5") (pin "G3") (pinfunction "VDD18_VCO_SXT_G3") (pintype "power_in"))
    )
    (net (code "22") (name "Net-(IC5F-DVDD_CGEN)") (class "Default")
      (node (ref "C202") (pin "1") (pinfunction "1_1") (pintype "passive"))
      (node (ref "C203") (pin "1") (pinfunction "1_1") (pintype "passive"))
      (node (ref "C204") (pin "1") (pinfunction "1_1") (pintype "passive"))
      (node (ref "FR69") (pin "1") (pinfunction "1_1") (pintype "passive"))
      (node (ref "IC5") (pin "A17") (pinfunction "DVDD_CGEN_A17") (pintype "power_in"))
      (node (ref "IC5") (pin "C25") (pinfunction "VDD12_DIG_C25") (pintype "power_in"))
      (node (ref "IC5") (pin "F24") (pinfunction "VDD_SPI_BUF_F24") (pintype "power_in"))
    )
    (net (code "23") (name "Net-(IC5F-DVDD_SXR)") (class "Default")
      (node (ref "C206") (pin "1") (pinfunction "1_1") (pintype "passive"))
      (node (ref "FR67") (pin "1") (pinfunction "1_1") (pintype "passive"))
      (node (ref "IC5") (pin "AL21") (pinfunction "DVDD_SXR_AL21") (pintype "power_in"))
    )
    (net (code "24") (name "Net-(IC5F-DVDD_SXT)") (class "Default")
      (node (ref "C205") (pin "2") (pinfunction "2_2") (pintype "passive"))
      (node (ref "FR68") (pin "1") (pinfunction "1_1") (pintype "passive"))
      (node (ref "IC5") (pin "M4") (pinfunction "DVDD_SXT_M4") (pintype "power_in"))
    )
    (net (code "25") (name "Net-(IC5F-VDD12O_VCO_SXT)") (class "Default")
      (node (ref "C227") (pin "2") (pinfunction "2_2") (pintype "passive"))
      (node (ref "FR70") (pin "1") (pinfunction "1_1") (pintype "passive"))
      (node (ref "IC5") (pin "J5") (pinfunction "VDD12O_VCO_SXT_J5") (pintype "power_in"))
      (node (ref "IC5") (pin "K6") (pinfunction "VDD12_VCO_SXT_K6") (pintype "power_in"))
    )
    (net (code "26") (name "Net-(IC5F-VDD12_LNA_RFE)") (class "Default")
      (node (ref "C224") (pin "1") (pinfunction "1_1") (pintype "passive"))
      (node (ref "FR74") (pin "1") (pinfunction "1_1") (pintype "passive"))
      (node (ref "IC5") (pin "AG5") (pinfunction "VDD12_LNA_RFE_AG5") (pintype "power_in"))
    )
    (net (code "27") (name "Net-(IC5F-VDD12_RXBUF)") (class "Default")
      (node (ref "C220") (pin "1") (pinfunction "1_1") (pintype "passive"))
      (node (ref "IC5") (pin "AP26") (pinfunction "VDD12_RXBUF_AP26") (pintype "power_in"))
      (node (ref "R101") (pin "1") (pinfunction "1_1") (pintype "passive"))
    )
    (net (code "28") (name "Net-(IC5F-VDD12_TIA_RFE)") (class "Default")
      (node (ref "C225") (pin "2") (pinfunction "2_2") (pintype "passive"))
      (node (ref "FR73") (pin "1") (pinfunction "1_1") (pintype "passive"))
      (node (ref "IC5") (pin "AD6") (pinfunction "VDD12_TIA_RFE_AD6") (pintype "power_in"))
    )
    (net (code "29") (name "Net-(IC5F-VDD12_TXBUF)") (class "Default")
      (node (ref "C213") (pin "1") (pinfunction "1_1") (pintype "passive"))
      (node (ref "IC5") (pin "G5") (pinfunction "VDD12_TXBUF_G5") (pintype "power_in"))
      (node (ref "R100") (pin "1") (pinfunction "1_1") (pintype "passive"))
    )
    (net (code "30") (name "Net-(IC5F-VDD12_VCO_SXR)") (class "Default")
      (node (ref "C221") (pin "1") (pinfunction "1_1") (pintype "passive"))
      (node (ref "FR77") (pin "1") (pinfunction "1_1") (pintype "passive"))
      (node (ref "IC5") (pin "AN23") (pinfunction "VDD12_VCO_SXR_AN23") (pintype "power_in"))
    )
    (net (code "31") (name "Net-(IC5F-VDD14_LNA_RFE)") (class "Default")
      (node (ref "C231") (pin "1") (pinfunction "1_1") (pintype "passive"))
      (node (ref "FR88") (pin "1") (pinfunction "1_1") (pintype "passive"))
      (node (ref "IC5") (pin "AF6") (pinfunction "VDD14_LNA_RFE_AF6") (pintype "power_in"))
    )
    (net (code "32") (name "Net-(IC5F-VDD14_RBB)") (class "Default")
      (node (ref "C233") (pin "1") (pinfunction "1_1") (pintype "passive"))
      (node (ref "FR86") (pin "1") (pinfunction "1_1") (pintype "passive"))
      (node (ref "IC5") (pin "AD4") (pinfunction "VDD14_RBB_AD4") (pintype "power_in"))
    )
    (net (code "33") (name "Net-(IC5F-VDD14_TIA_RFE)") (class "Default")
      (node (ref "C232") (pin "1") (pinfunction "1_1") (pintype "passive"))
      (node (ref "FR87") (pin "1") (pinfunction "1_1") (pintype "passive"))
      (node (ref "IC5") (pin "AF2") (pinfunction "VDD14_TIA_RFE_AF2") (pintype "power_in"))
    )
    (net (code "34") (name "Net-(IC5F-VDD14_VCO_CGEN)") (class "Default")
      (node (ref "C230") (pin "1") (pinfunction "1_1") (pintype "passive"))
      (node (ref "FR89") (pin "1") (pinfunction "1_1") (pintype "passive"))
      (node (ref "IC5") (pin "C21") (pinfunction "VDD14_VCO_CGEN_C21") (pintype "power_in"))
    )
    (net (code "35") (name "Net-(IC5F-VDDO_DIV_SXT)") (class "Default")
      (node (ref "C229") (pin "1") (pinfunction "1_1") (pintype "passive"))
      (node (ref "FR84") (pin "1") (pinfunction "1_1") (pintype "passive"))
      (node (ref "IC5") (pin "K2") (pinfunction "VDDO_DIV_SXT_K2") (pintype "power_in"))
      (node (ref "IC5") (pin "L5") (pinfunction "VDD_DIV_SXT_L5") (pintype "power_in"))
    )
    (net (code "36") (name "Net-(IC5F-VDDO_TLOBUF_TRF)") (class "Default")
      (node (ref "C215") (pin "1") (pinfunction "1_1") (pintype "passive"))
      (node (ref "FR83") (pin "1") (pinfunction "1_1") (pintype "passive"))
      (node (ref "IC5") (pin "D6") (pinfunction "VDDO_TLOBUF_TRF_D6") (pintype "power_in"))
      (node (ref "IC5") (pin "F8") (pinfunction "VDD_TLOBUF_TRF_F8") (pintype "power_in"))
    )
    (net (code "37") (name "Net-(IC5F-VDD_AFE)") (class "Default")
      (node (ref "C219") (pin "1") (pinfunction "1_1") (pintype "passive"))
      (node (ref "FR79") (pin "1") (pinfunction "1_1") (pintype "passive"))
      (node (ref "IC5") (pin "AJ25") (pinfunction "VDD_AFE_AJ25") (pintype "power_in"))
    )
    (net (code "38") (name "Net-(IC5F-VDD_CP_CGEN)") (class "Default")
      (node (ref "C218") (pin "2") (pinfunction "2_2") (pintype "passive"))
      (node (ref "FR80") (pin "1") (pinfunction "1_1") (pintype "passive"))
      (node (ref "IC5") (pin "F20") (pinfunction "VDD_CP_CGEN_F20") (pintype "power_in"))
    )
    (net (code "39") (name "Net-(IC5F-VDD_CP_SXR)") (class "Default")
      (node (ref "C223") (pin "1") (pinfunction "1_1") (pintype "passive"))
      (node (ref "FR75") (pin "1") (pinfunction "1_1") (pintype "passive"))
      (node (ref "IC5") (pin "AL19") (pinfunction "VDD_CP_SXR_AL19") (pintype "power_in"))
    )
    (net (code "40") (name "Net-(IC5F-VDD_CP_SXT)") (class "Default")
      (node (ref "C226") (pin "1") (pinfunction "1_1") (pintype "passive"))
      (node (ref "FR71") (pin "1") (pinfunction "1_1") (pintype "passive"))
      (node (ref "IC5") (pin "J3") (pinfunction "VDD_CP_SXT_J3") (pintype "power_in"))
    )
    (net (code "41") (name "Net-(IC5F-VDD_DIV_CGEN)") (class "Default")
      (node (ref "C217") (pin "1") (pinfunction "1_1") (pintype "passive"))
      (node (ref "FR81") (pin "1") (pinfunction "1_1") (pintype "passive"))
      (node (ref "IC5") (pin "E19") (pinfunction "VDD_DIV_CGEN_E19") (pintype "power_in"))
    )
    (net (code "42") (name "Net-(IC5F-VDD_DIV_SXR)") (class "Default")
      (node (ref "C222") (pin "1") (pinfunction "1_1") (pintype "passive"))
      (node (ref "FR76") (pin "1") (pinfunction "1_1") (pintype "passive"))
      (node (ref "IC5") (pin "AM20") (pinfunction "VDD_DIV_SXR_AM20") (pintype "power_in"))
    )
    (net (code "43") (name "Net-(IC5F-VDD_MXLOBUF_RFE)") (class "Default")
      (node (ref "C234") (pin "1") (pinfunction "1_1") (pintype "passive"))
      (node (ref "FR85") (pin "1") (pinfunction "1_1") (pintype "passive"))
      (node (ref "IC5") (pin "AN17") (pinfunction "VDD_MXLOBUF_RFE_AN17") (pintype "power_in"))
    )
    (net (code "44") (name "Net-(IC5F-VDD_TBB)") (class "Default")
      (node (ref "C214") (pin "1") (pinfunction "1_1") (pintype "passive"))
      (node (ref "FR72") (pin "1") (pinfunction "1_1") (pintype "passive"))
      (node (ref "IC5") (pin "P4") (pinfunction "VDD_TBB_P4") (pintype "power_in"))
    )
    (net (code "45") (name "Net-(IC5F-VDD_TPAD_TRF)") (class "Default")
      (node (ref "C216") (pin "1") (pinfunction "1_1") (pintype "passive"))
      (node (ref "FR82") (pin "1") (pinfunction "1_1") (pintype "passive"))
      (node (ref "IC5") (pin "B16") (pinfunction "VDD_TPAD_TRF_B16") (pintype "power_in"))
    )
    (net (code "46") (name "VCC1P4_LMS3") (class "Default")
      (node (ref "FR84") (pin "2") (pinfunction "2_2") (pintype "passive"))
      (node (ref "FR85") (pin "2") (pinfunction "2_2") (pintype "passive"))
      (node (ref "FR86") (pin "2") (pinfunction "2_2") (pintype "passive"))
      (node (ref "FR87") (pin "2") (pinfunction "2_2") (pintype "passive"))
      (node (ref "FR88") (pin "2") (pinfunction "2_2") (pintype "passive"))
      (node (ref "FR89") (pin "2") (pinfunction "2_2") (pintype "passive"))
      (node (ref "R98") (pin "1") (pinfunction "1_1") (pintype "passive"))
    )
    (net (code "47") (name "VCC1P8_LMS3") (class "Default")
      (node (ref "FR90") (pin "2") (pinfunction "2_2") (pintype "passive"))
      (node (ref "FR91") (pin "1") (pinfunction "1_1") (pintype "passive"))
      (node (ref "FR92") (pin "1") (pinfunction "1_1") (pintype "passive"))
      (node (ref "FR93") (pin "2") (pinfunction "2_2") (pintype "passive"))
      (node (ref "FR94") (pin "2") (pinfunction "2_2") (pintype "passive"))
      (node (ref "FR95") (pin "2") (pinfunction "2_2") (pintype "passive"))
      (node (ref "FR96") (pin "2") (pinfunction "2_2") (pintype "passive"))
      (node (ref "FR97") (pin "2") (pinfunction "2_2") (pintype "passive"))
      (node (ref "R102") (pin "2") (pinfunction "2_2") (pintype "passive"))
      (node (ref "R108") (pin "2") (pinfunction "2_2") (pintype "passive"))
      (node (ref "R109") (pin "1") (pinfunction "1_1") (pintype "passive"))
    )
    (net (code "48") (name "VCC1P25_LMS3") (class "Default")
      (node (ref "FR67") (pin "2") (pinfunction "2_2") (pintype "passive"))
      (node (ref "FR68") (pin "2") (pinfunction "2_2") (pintype "passive"))
      (node (ref "FR69") (pin "2") (pinfunction "2_2") (pintype "passive"))
      (node (ref "FR70") (pin "2") (pinfunction "2_2") (pintype "passive"))
      (node (ref "FR71") (pin "2") (pinfunction "2_2") (pintype "passive"))
      (node (ref "FR72") (pin "2") (pinfunction "2_2") (pintype "passive"))
      (node (ref "FR73") (pin "2") (pinfunction "2_2") (pintype "passive"))
      (node (ref "FR74") (pin "2") (pinfunction "2_2") (pintype "passive"))
      (node (ref "FR75") (pin "2") (pinfunction "2_2") (pintype "passive"))
      (node (ref "FR76") (pin "2") (pinfunction "2_2") (pintype "passive"))
      (node (ref "FR77") (pin "2") (pinfunction "2_2") (pintype "passive"))
      (node (ref "FR78") (pin "2") (pinfunction "2_2") (pintype "passive"))
      (node (ref "FR79") (pin "2") (pinfunction "2_2") (pintype "passive"))
      (node (ref "FR80") (pin "2") (pinfunction "2_2") (pintype "passive"))
      (node (ref "FR81") (pin "2") (pinfunction "2_2") (pintype "passive"))
      (node (ref "FR82") (pin "2") (pinfunction "2_2") (pintype "passive"))
      (node (ref "FR83") (pin "2") (pinfunction "2_2") (pintype "passive"))
      (node (ref "R99") (pin "1") (pinfunction "1_1") (pintype "passive"))
    )
    (net (code "49") (name "VDIO_LMS") (class "Default")
      (node (ref "C236") (pin "2") (pinfunction "2_2") (pintype "passive"))
      (node (ref "R103") (pin "1") (pinfunction "1_1") (pintype "passive"))
      (node (ref "R104") (pin "1") (pinfunction "1_1") (pintype "passive"))
      (node (ref "R105") (pin "1") (pinfunction "1_1") (pintype "passive"))
      (node (ref "R106") (pin "1") (pinfunction "1_1") (pintype "passive"))
      (node (ref "R107") (pin "1") (pinfunction "1_1") (pintype "passive"))
    )
  )
)
